# 2020-08-16_06-31-521.net
KiCad netlist of a schematic drawn in Altium Designer
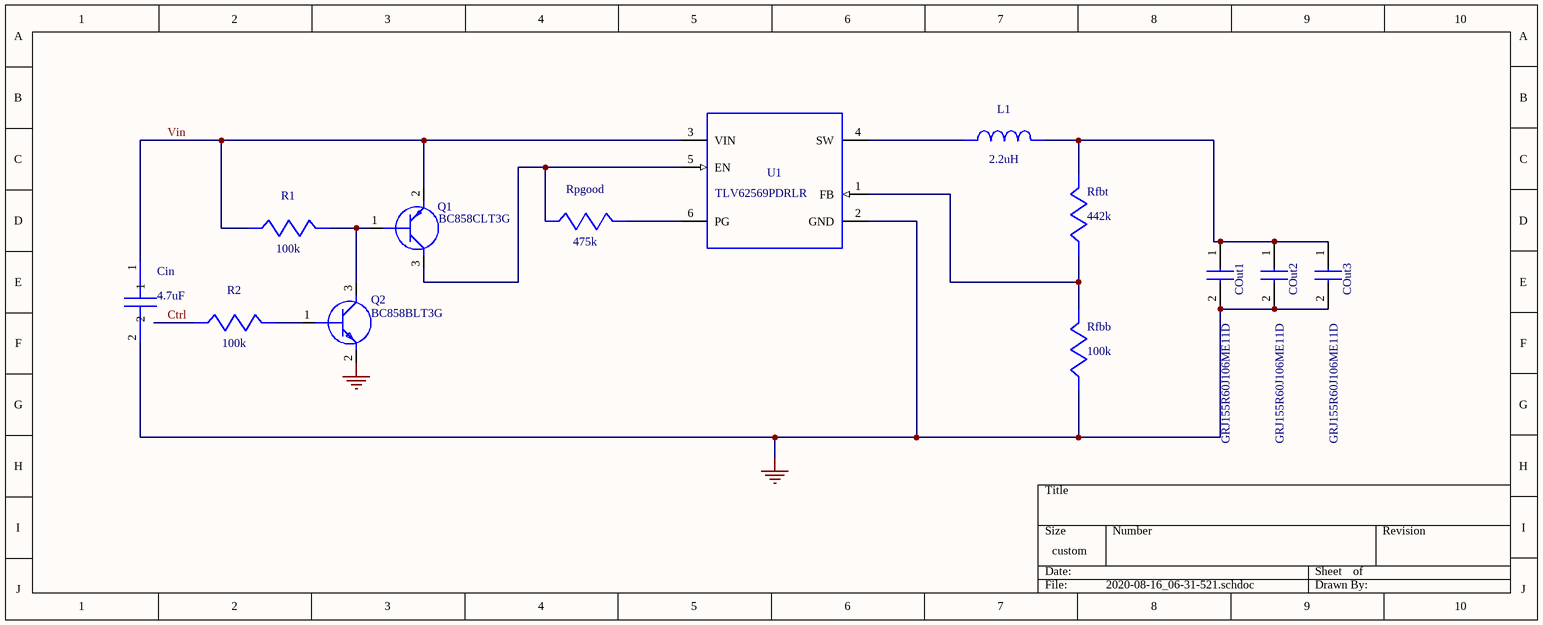
[diagram p0: 2020-08-16_06-31-521.schdoc]

(export (version "E")
  (design (tool "Eeschema 10.0.6"))
  (components
    (comp (ref "Cin")
      (value "4.7uF")
      (description "GRM155R61A475MEA")
      (fields
        (field (name "MANUFACTURER PART NUMBER") "GRM155R61A475MEAAD")
        (field (name "Comment") "Comment")
      )
      (libsource (lib "TI WEBENCH") (part "Cin"))
    )
    (comp (ref "COut1")
      (value "GRJ155R60J106ME11D")
      (footprint "SamacSys:CAPC1005X70N")
      (description "Capacitor")
      (fields (field (name "MOUSER2 PART NUMBER") "81-GRJ155R60J106ME1D"))
      (libsource (lib "*") (part "GRJ155R60J106ME11D"))
    )
    (comp (ref "COut2")
      (value "GRJ155R60J106ME11D")
      (footprint "SamacSys:CAPC1005X70N")
      (description "Capacitor")
      (fields (field (name "MOUSER2 PART NUMBER") "81-GRJ155R60J106ME1D"))
      (libsource (lib "*") (part "GRJ155R60J106ME11D"))
    )
    (comp (ref "COut3")
      (value "GRJ155R60J106ME11D")
      (footprint "SamacSys:CAPC1005X70N")
      (description "Capacitor")
      (fields (field (name "MOUSER2 PART NUMBER") "81-GRJ155R60J106ME1D"))
      (libsource (lib "*") (part "GRJ155R60J106ME11D"))
    )
    (comp (ref "L1")
      (value "2.2uH")
      (description "Unknown")
      (fields
        (field (name "MANUFACTURER PART NUMBER") "IHLP2020CZER2R2M11")
        (field (name "Comment") "Comment")
      )
      (libsource (lib "TI WEBENCH") (part "L1"))
    )
    (comp (ref "Q1")
      (value "BC858CLT3G")
      (footprint "SamacSys:BC858CLT3G")
      (description "Transistor BJT PNP")
      (fields (field (name "MOUSER2 PART NUMBER") "863-BC858CLT3G"))
      (libsource (lib "SamacSys") (part "BC858CLT3G"))
    )
    (comp (ref "Q2")
      (value "BC858BLT3G")
      (footprint "SamacSys:SOT96P237X111-3N")
      (description "Transistor BJT PNP")
      (libsource (lib "SamacSys") (part "BC858BLT3G"))
    )
    (comp (ref "R1") (value "100k") (description "RR1220P-104-D") (libsource (lib "TI WEBENCH") (part "Rpg")))
    (comp (ref "R2") (value "100k") (description "RR1220P-104-D") (libsource (lib "TI WEBENCH") (part "Rpg")))
    (comp (ref "Rfbb")
      (value "100k")
      (description "CRCW0402100KFKED")
      (fields (field (name "Comment") "Comment"))
      (libsource (lib "TI WEBENCH") (part "Rfbb"))
    )
    (comp (ref "Rfbt")
      (value "442k")
      (description "RC0201FR-07442KL")
      (fields (field (name "Comment") "Comment"))
      (libsource (lib "TI WEBENCH") (part "Rfbt"))
    )
    (comp (ref "Rpgood")
      (value "475k")
      (description "CRCW0402475KFKED")
      (fields (field (name "Comment") "Comment"))
      (libsource (lib "TI WEBENCH") (part "Rpgood"))
    )
    (comp (ref "U1")
      (value "Comment")
      (description "TLV62569PDRLR")
      (fields (field (name "PACKAGEREFERENCE") "TLV62569PDRLR"))
      (libsource (lib "TI WEBENCH") (part "U1"))
    )
  )
  (nets
    (net (code "1") (name "/Ctrl") (class "Default")
      (node (ref "R2") (pin "2") (pinfunction "2_2") (pintype "passive"))
    )
    (net (code "2") (name "/Vin") (class "Default")
      (node (ref "Cin") (pin "1") (pinfunction "1_1") (pintype "passive"))
      (node (ref "Q1") (pin "2") (pinfunction "E_2") (pintype "passive"))
      (node (ref "R1") (pin "2") (pinfunction "2_2") (pintype "passive"))
      (node (ref "U1") (pin "3") (pinfunction "VIN_3") (pintype "power_in"))
    )
    (net (code "3") (name "0") (class "Default")
      (node (ref "COut1") (pin "2") (pinfunction "2_2") (pintype "passive"))
      (node (ref "COut2") (pin "2") (pinfunction "2_2") (pintype "passive"))
      (node (ref "COut3") (pin "2") (pinfunction "2_2") (pintype "passive"))
      (node (ref "Cin") (pin "2") (pinfunction "2_2") (pintype "passive"))
      (node (ref "Q2") (pin "2") (pinfunction "E_2") (pintype "passive"))
      (node (ref "Rfbb") (pin "2") (pinfunction "2_2") (pintype "passive"))
      (node (ref "U1") (pin "2") (pinfunction "GND_2") (pintype "power_in"))
    )
    (net (code "4") (name "Net-(COut1-Pad1)") (class "Default")
      (node (ref "COut1") (pin "1") (pinfunction "1_1") (pintype "passive"))
      (node (ref "COut2") (pin "1") (pinfunction "1_1") (pintype "passive"))
      (node (ref "COut3") (pin "1") (pinfunction "1_1") (pintype "passive"))
      (node (ref "L1") (pin "2") (pinfunction "2_2") (pintype "passive"))
      (node (ref "Rfbt") (pin "1") (pinfunction "1_1") (pintype "passive"))
    )
    (net (code "5") (name "Net-(Q1-B)") (class "Default")
      (node (ref "Q1") (pin "1") (pinfunction "B_1") (pintype "passive"))
      (node (ref "Q2") (pin "3") (pinfunction "C_3") (pintype "passive"))
      (node (ref "R1") (pin "1") (pinfunction "1_1") (pintype "passive"))
    )
    (net (code "6") (name "Net-(Q1-C)") (class "Default")
      (node (ref "Q1") (pin "3") (pinfunction "C_3") (pintype "passive"))
      (node (ref "Rpgood") (pin "2") (pinfunction "2_2") (pintype "passive"))
      (node (ref "U1") (pin "5") (pinfunction "EN_5") (pintype "input"))
    )
    (net (code "7") (name "Net-(Q2-B)") (class "Default")
      (node (ref "Q2") (pin "1") (pinfunction "B_1") (pintype "passive"))
      (node (ref "R2") (pin "1") (pinfunction "1_1") (pintype "passive"))
    )
    (net (code "8") (name "Net-(U1-FB)") (class "Default")
      (node (ref "Rfbb") (pin "1") (pinfunction "1_1") (pintype "passive"))
      (node (ref "Rfbt") (pin "2") (pinfunction "2_2") (pintype "passive"))
      (node (ref "U1") (pin "1") (pinfunction "FB_1") (pintype "input"))
    )
    (net (code "9") (name "Net-(U1-PG)") (class "Default")
      (node (ref "Rpgood") (pin "1") (pinfunction "1_1") (pintype "passive"))
      (node (ref "U1") (pin "6") (pinfunction "PG_6") (pintype "open_collector"))
    )
    (net (code "10") (name "Net-(U1-SW)") (class "Default")
      (node (ref "L1") (pin "1") (pinfunction "1_1") (pintype "passive"))
      (node (ref "U1") (pin "4") (pinfunction "SW_4") (pintype "power_in"))
    )
  )
)
